# design.net
KiCad netlist of a schematic drawn in Altium Designer
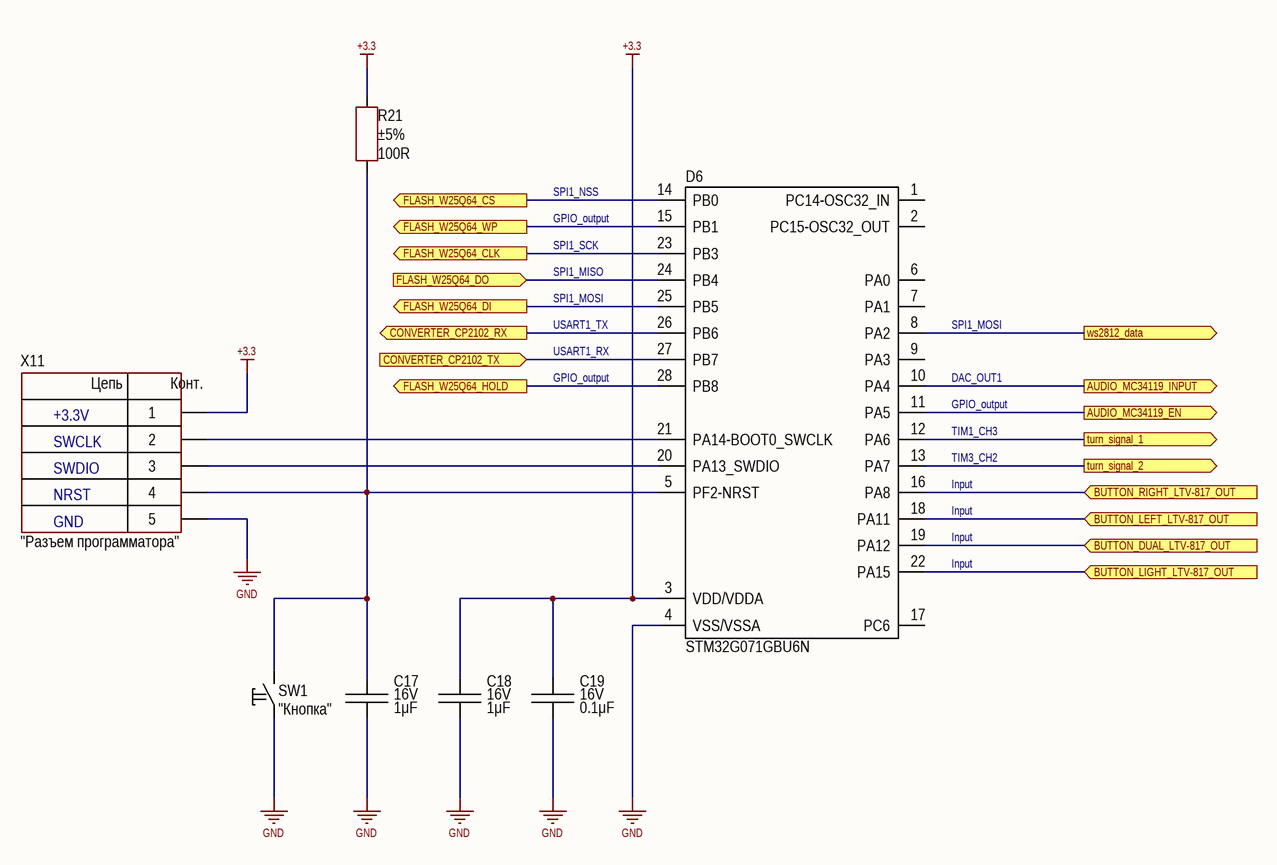
[diagram p0: Микроконтроллер.SchDoc]

(export (version "E")
  (design (tool "Eeschema 10.0.6"))
  (components
    (comp (ref "C17")
      (value "1μF")
      (footprint "CAP: 0603")
      (fields
        (field (name "MANUFACTURER") "Yageo")
        (field (name "PARTNUMBER") "CC0603KRX7R7BB104")
        (field (name "VALUEMANUFACTURERPARTNUMBER") "Ceramic capacitor, 1μF, X7R, ±10%, 16V, 0603, -55...+125°C")
        (field (name "VOLTAGE") "16V")
      )
      (libsource (lib "capacitor") (part "Ceramic_0603"))
    )
    (comp (ref "C18")
      (value "1μF")
      (footprint "CAP: 0603")
      (fields
        (field (name "MANUFACTURER") "Yageo")
        (field (name "PARTNUMBER") "CC0603KRX7R7BB104")
        (field (name "VALUEMANUFACTURERPARTNUMBER") "Ceramic capacitor, 1μF, X7R, ±10%, 16V, 0603, -55...+125°C")
        (field (name "VOLTAGE") "16V")
      )
      (libsource (lib "capacitor") (part "Ceramic_0603"))
    )
    (comp (ref "C19")
      (value "0.1μF")
      (footprint "CAP: 0603")
      (fields
        (field (name "MANUFACTURER") "Yageo")
        (field (name "PARTNUMBER") "CC0603KRX7R7BB104")
        (field (name "VALUEMANUFACTURERPARTNUMBER") "Ceramic capacitor, 0.1μF, X7R, ±10%, 16V, 0603, -55...+125°C")
        (field (name "VOLTAGE") "16V")
      )
      (libsource (lib "capacitor") (part "Ceramic_0603"))
    )
    (comp (ref "D6")
      (value "~")
      (footprint "28-UFQFPN")
      (description "Cortex-M0")
      (fields
        (field (name "MANUFACTURER") "STMicroelectronics")
        (field (name "VALUEMANUFACTURERPARTNUMBER") "IC microcontroller, 32-Bit, Cortex-M0, 64 MHz, 128KB, 32KB, 2.4...3.6V, -40...+85°C, QFN-28")
        (field (name "PARTNUMBER") "STM32G071GBU6N")
      )
      (libsource (lib "ic-mcu") (part "STM32G071GBU6N"))
    )
    (comp (ref "R21")
      (value "100R")
      (footprint "RES: 0603")
      (fields
        (field (name "MANUFACTURER") "Yageo")
        (field (name "PARTNUMBER") "RC0603JR-07100RL")
        (field (name "VALUEMANUFACTURERPARTNUMBER") "Resistor film, 100R, ±5%, 0603, 0.1W, -55...+125°C")
        (field (name "TOLERANCE") "±5%")
      )
      (libsource (lib "resistor") (part "Resistor_0603"))
    )
    (comp (ref "SW1")
      (value "~")
      (footprint "BUT: 3x4x2 SMT")
      (description "SMT 3*4*2 2PIN")
      (fields
        (field (name "MANUFACTURER") "xin cheng electronic")
        (field (name "VALUEMANUFACTURERPARTNUMBER") ", 3*4*2mm")
        (field (name "COMMENTTEXT") "\"Кнопка\"")
      )
      (libsource (lib "electromechanics") (part "Button_3x4x2_SMT"))
    )
    (comp (ref "X11")
      (value "~")
      (footprint "CON: PLS-5")
      (fields
        (field (name "MANUFACTURER") "Connfly")
        (field (name "VALUEMANUFACTURERPARTNUMBER") "Connector, 5pin, 2.54mm, 500VAC, 3A")
        (field (name "PARTNUMBER") "PLS-5")
        (field (name "COMMENTTEXT") "\"Разъем программатора\"")
      )
      (libsource (lib "connector") (part "PLS-5"))
    )
  )
  (nets
    (net (code "1") (name "+3.3") (class "Default")
      (node (ref "C18") (pin "2") (pinfunction "2_2") (pintype "passive"))
      (node (ref "C19") (pin "2") (pinfunction "2_2") (pintype "passive"))
      (node (ref "D6") (pin "3") (pinfunction "VDD/VDDA_3") (pintype "passive"))
      (node (ref "R21") (pin "2") (pinfunction "2_2") (pintype "passive"))
      (node (ref "X11") (pin "1") (pinfunction "1_1") (pintype "passive"))
    )
    (net (code "2") (name "/AUDIO_MC34119_EN") (class "Default")
      (node (ref "D6") (pin "11") (pinfunction "PA5_11") (pintype "passive"))
    )
    (net (code "3") (name "/AUDIO_MC34119_INPUT") (class "Default")
      (node (ref "D6") (pin "10") (pinfunction "PA4_10") (pintype "passive"))
    )
    (net (code "4") (name "/BUTTON_DUAL_LTV-817_OUT") (class "Default")
      (node (ref "D6") (pin "19") (pinfunction "PA12_19") (pintype "passive"))
    )
    (net (code "5") (name "/BUTTON_LEFT_LTV-817_OUT") (class "Default")
      (node (ref "D6") (pin "18") (pinfunction "PA11_18") (pintype "passive"))
    )
    (net (code "6") (name "/BUTTON_LIGHT_LTV-817_OUT") (class "Default")
      (node (ref "D6") (pin "22") (pinfunction "PA15_22") (pintype "passive"))
    )
    (net (code "7") (name "/BUTTON_RIGHT_LTV-817_OUT") (class "Default")
      (node (ref "D6") (pin "16") (pinfunction "PA8_16") (pintype "passive"))
    )
    (net (code "8") (name "/CONVERTER_CP2102_RX") (class "Default")
      (node (ref "D6") (pin "26") (pinfunction "PB6_26") (pintype "passive"))
    )
    (net (code "9") (name "/CONVERTER_CP2102_TX") (class "Default")
      (node (ref "D6") (pin "27") (pinfunction "PB7_27") (pintype "passive"))
    )
    (net (code "10") (name "/FLASH_W25Q64_CLK") (class "Default")
      (node (ref "D6") (pin "23") (pinfunction "PB3_23") (pintype "passive"))
    )
    (net (code "11") (name "/FLASH_W25Q64_CS") (class "Default")
      (node (ref "D6") (pin "14") (pinfunction "PB0_14") (pintype "passive"))
    )
    (net (code "12") (name "/FLASH_W25Q64_DI") (class "Default")
      (node (ref "D6") (pin "25") (pinfunction "PB5_25") (pintype "passive"))
    )
    (net (code "13") (name "/FLASH_W25Q64_DO") (class "Default")
      (node (ref "D6") (pin "24") (pinfunction "PB4_24") (pintype "passive"))
    )
    (net (code "14") (name "/FLASH_W25Q64_HOLD") (class "Default")
      (node (ref "D6") (pin "28") (pinfunction "PB8_28") (pintype "passive"))
    )
    (net (code "15") (name "/FLASH_W25Q64_WP") (class "Default")
      (node (ref "D6") (pin "15") (pinfunction "PB1_15") (pintype "passive"))
    )
    (net (code "16") (name "/turn_signal_1") (class "Default")
      (node (ref "D6") (pin "12") (pinfunction "PA6_12") (pintype "passive"))
    )
    (net (code "17") (name "/turn_signal_2") (class "Default")
      (node (ref "D6") (pin "13") (pinfunction "PA7_13") (pintype "passive"))
    )
    (net (code "18") (name "/ws2812_data") (class "Default")
      (node (ref "D6") (pin "8") (pinfunction "PA2_8") (pintype "passive"))
    )
    (net (code "19") (name "GND") (class "Default")
      (node (ref "C17") (pin "1") (pinfunction "1_1") (pintype "passive"))
      (node (ref "C18") (pin "1") (pinfunction "1_1") (pintype "passive"))
      (node (ref "C19") (pin "1") (pinfunction "1_1") (pintype "passive"))
      (node (ref "D6") (pin "4") (pinfunction "VSS/VSSA_4") (pintype "passive"))
      (node (ref "SW1") (pin "1") (pinfunction "1_1") (pintype "passive"))
      (node (ref "X11") (pin "5") (pinfunction "5_5") (pintype "power_in"))
    )
    (net (code "20") (name "Net-(D6-PA13_SWDIO)") (class "Default")
      (node (ref "D6") (pin "20") (pinfunction "PA13_SWDIO_20") (pintype "passive"))
      (node (ref "X11") (pin "3") (pinfunction "3_3") (pintype "power_in"))
    )
    (net (code "21") (name "Net-(D6-PA14-BOOT0_SWCLK)") (class "Default")
      (node (ref "D6") (pin "21") (pinfunction "PA14-BOOT0_SWCLK_21") (pintype "passive"))
      (node (ref "X11") (pin "2") (pinfunction "2_2") (pintype "passive"))
    )
    (net (code "22") (name "Net-(D6-PF2-NRST)") (class "Default")
      (node (ref "C17") (pin "2") (pinfunction "2_2") (pintype "passive"))
      (node (ref "D6") (pin "5") (pinfunction "PF2-NRST_5") (pintype "passive"))
      (node (ref "R21") (pin "1") (pinfunction "1_1") (pintype "passive"))
      (node (ref "SW1") (pin "2") (pinfunction "2_2") (pintype "passive"))
      (node (ref "X11") (pin "4") (pinfunction "4_4") (pintype "power_in"))
    )
    (net (code "23") (name "unconnected-(D6-PA0-Pad6)") (class "Default")
      (node (ref "D6") (pin "6") (pinfunction "PA0_6") (pintype "passive"))
    )
    (net (code "24") (name "unconnected-(D6-PA1-Pad7)") (class "Default")
      (node (ref "D6") (pin "7") (pinfunction "PA1_7") (pintype "passive"))
    )
    (net (code "25") (name "unconnected-(D6-PA3-Pad9)") (class "Default")
      (node (ref "D6") (pin "9") (pinfunction "PA3_9") (pintype "passive"))
    )
    (net (code "26") (name "unconnected-(D6-PC6-Pad17)") (class "Default")
      (node (ref "D6") (pin "17") (pinfunction "PC6_17") (pintype "passive"))
    )
    (net (code "27") (name "unconnected-(D6-PC14-OSC32_IN-Pad1)") (class "Default")
      (node (ref "D6") (pin "1") (pinfunction "PC14-OSC32_IN_1") (pintype "passive"))
    )
    (net (code "28") (name "unconnected-(D6-PC15-OSC32_OUT-Pad2)") (class "Default")
      (node (ref "D6") (pin "2") (pinfunction "PC15-OSC32_OUT_2") (pintype "passive"))
    )
  )
)
